# GasSensorCentral_v2_2.net
KiCad netlist of a schematic drawn in EAGLE
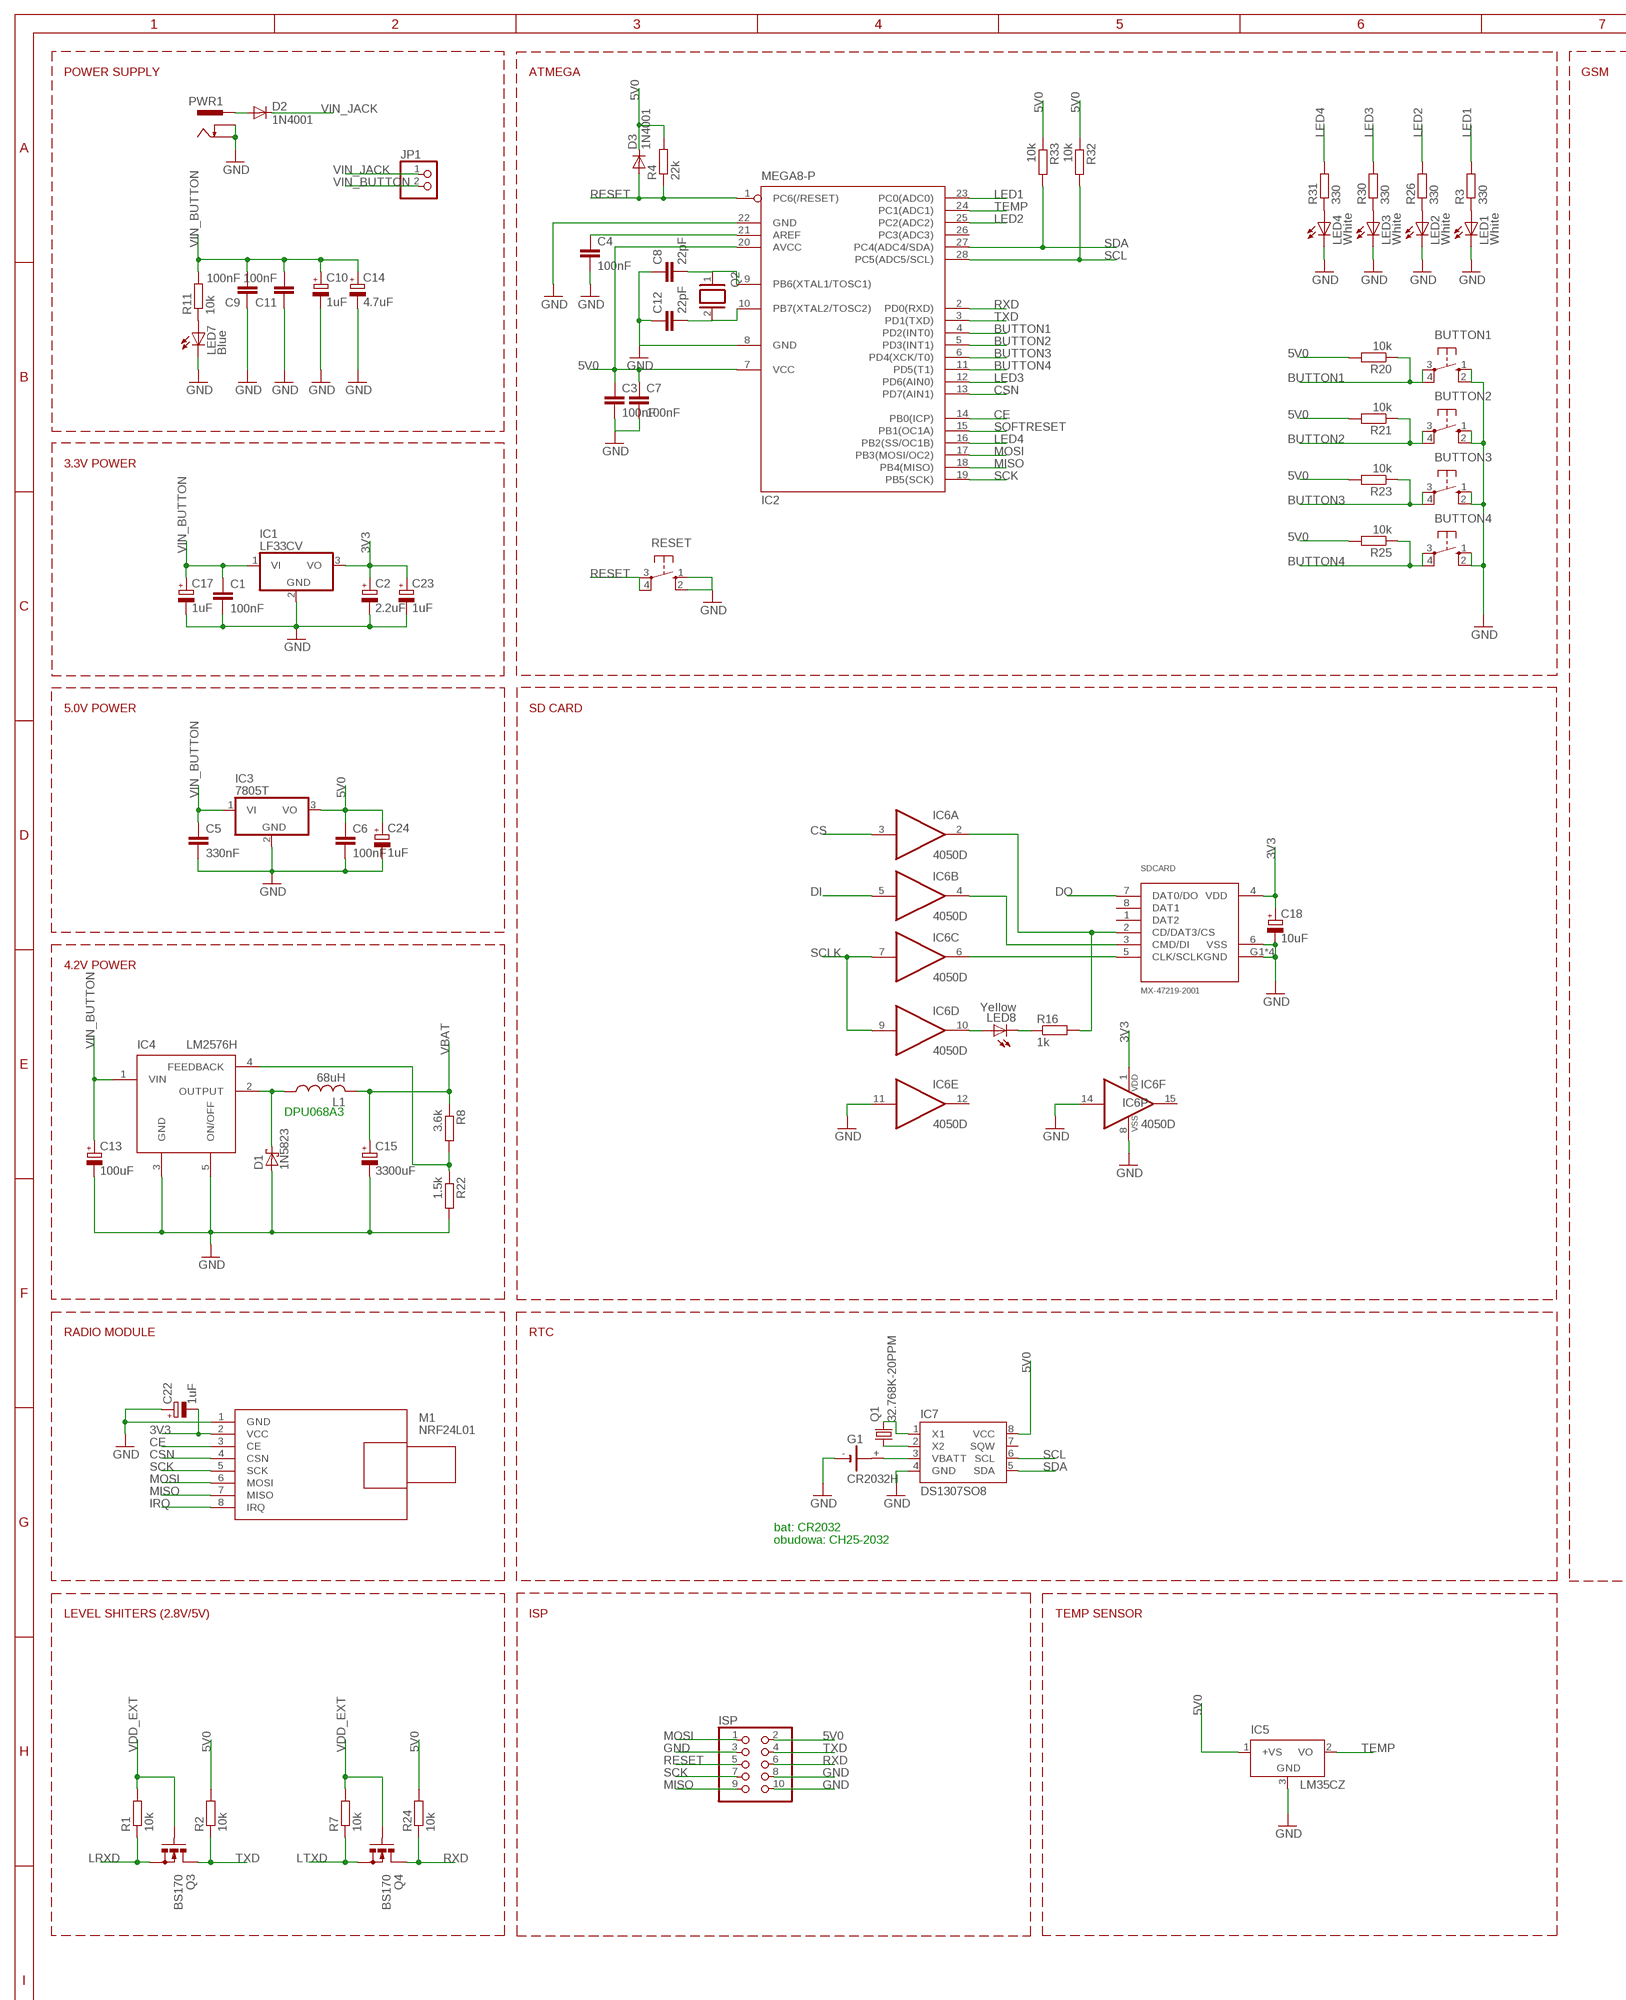
[diagram p0: schematic, sheet 1, part 1 of 2]
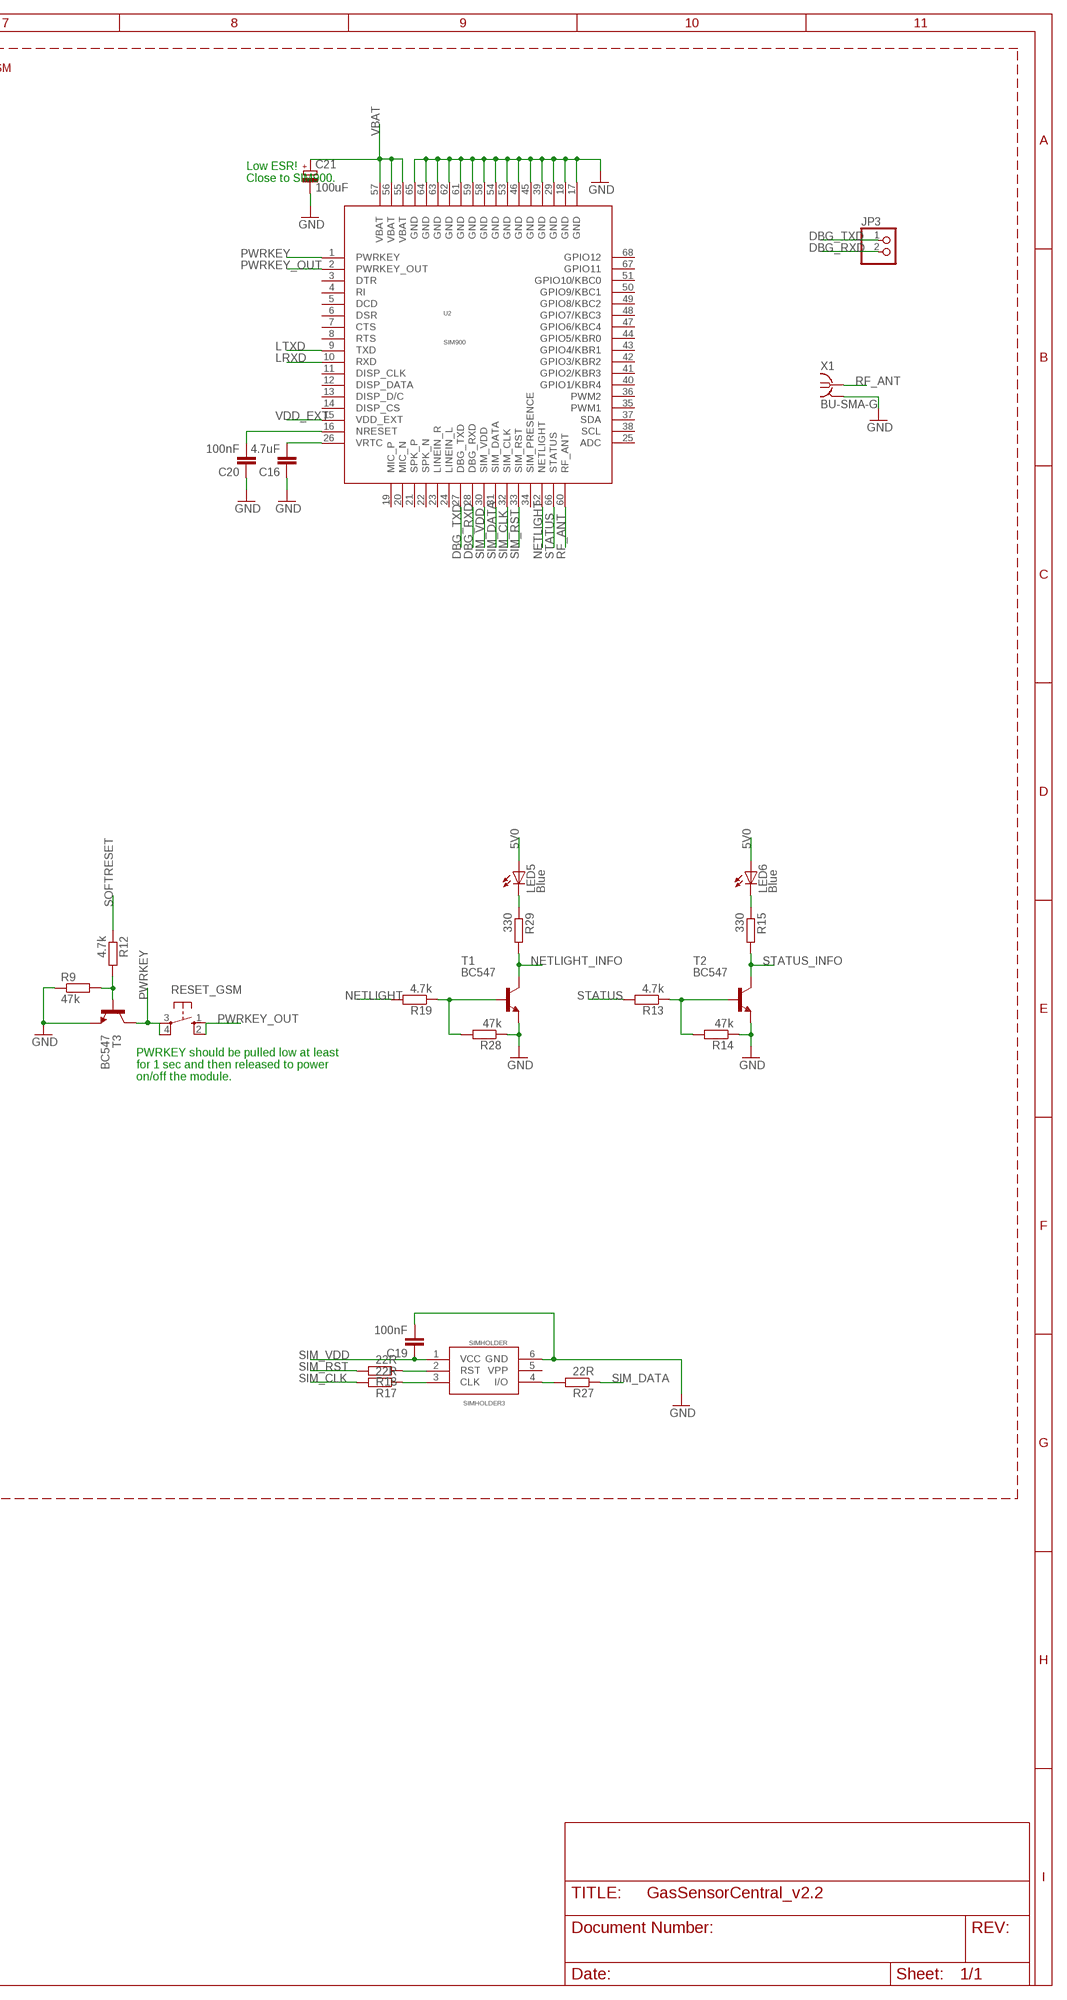
[diagram p1: schematic, sheet 1, part 2 of 2]

(export (version "E")
  (design (tool "Eeschema 10.0.6"))
  (components
    (comp (ref "BUTTON1")
      (value "10-XX")
      (footprint "eagle-import:B3F-10XX")
      (fields (field (name "MPN") "B3F-1000"))
      (libsource (lib "eagle-import") (part "10-XX"))
    )
    (comp (ref "BUTTON2")
      (value "10-XX")
      (footprint "eagle-import:B3F-10XX")
      (fields (field (name "MPN") "B3F-1000"))
      (libsource (lib "eagle-import") (part "10-XX"))
    )
    (comp (ref "BUTTON3")
      (value "10-XX")
      (footprint "eagle-import:B3F-10XX")
      (fields (field (name "MPN") "B3F-1000"))
      (libsource (lib "eagle-import") (part "10-XX"))
    )
    (comp (ref "BUTTON4")
      (value "10-XX")
      (footprint "eagle-import:B3F-10XX")
      (fields (field (name "MPN") "B3F-1000"))
      (libsource (lib "eagle-import") (part "10-XX"))
    )
    (comp (ref "C1")
      (value "100nF")
      (footprint "eagle-import:C025-025X050")
      (libsource (lib "eagle-import") (part "C-EU025-025X050"))
    )
    (comp (ref "C2")
      (value "2.2uF")
      (footprint "eagle-import:E2,5-5")
      (libsource (lib "eagle-import") (part "CPOL-EUE2.5-5"))
    )
    (comp (ref "C3")
      (value "100nF")
      (footprint "eagle-import:C025-025X050")
      (libsource (lib "eagle-import") (part "C-EU025-025X050"))
    )
    (comp (ref "C4")
      (value "100nF")
      (footprint "eagle-import:C025-025X050")
      (libsource (lib "eagle-import") (part "C-EU025-025X050"))
    )
    (comp (ref "C5")
      (value "330nF")
      (footprint "eagle-import:C025-025X050")
      (libsource (lib "eagle-import") (part "C-EU025-025X050"))
    )
    (comp (ref "C6")
      (value "100nF")
      (footprint "eagle-import:C025-025X050")
      (libsource (lib "eagle-import") (part "C-EU025-025X050"))
    )
    (comp (ref "C7")
      (value "100nF")
      (footprint "eagle-import:C025-025X050")
      (libsource (lib "eagle-import") (part "C-EU025-025X050"))
    )
    (comp (ref "C8")
      (value "22pF")
      (footprint "eagle-import:C025-025X050")
      (libsource (lib "eagle-import") (part "C-EU025-025X050"))
    )
    (comp (ref "C9")
      (value "100nF")
      (footprint "eagle-import:C025-025X050")
      (libsource (lib "eagle-import") (part "C-EU025-025X050"))
    )
    (comp (ref "C10")
      (value "1uF")
      (footprint "eagle-import:E2,5-5")
      (libsource (lib "eagle-import") (part "CPOL-EUE2.5-5"))
    )
    (comp (ref "C11")
      (value "100nF")
      (footprint "eagle-import:C025-025X050")
      (libsource (lib "eagle-import") (part "C-EU025-025X050"))
    )
    (comp (ref "C12")
      (value "22pF")
      (footprint "eagle-import:C025-025X050")
      (libsource (lib "eagle-import") (part "C-EU025-025X050"))
    )
    (comp (ref "C13")
      (value "100uF")
      (footprint "eagle-import:E2,5-5")
      (libsource (lib "eagle-import") (part "CPOL-EUE2.5-5"))
    )
    (comp (ref "C14")
      (value "4.7uF")
      (footprint "eagle-import:E2,5-5")
      (libsource (lib "eagle-import") (part "CPOL-EUE2.5-5"))
    )
    (comp (ref "C15")
      (value "3300uF")
      (footprint "eagle-import:E5-13")
      (libsource (lib "eagle-import") (part "CPOL-EUE5-13"))
    )
    (comp (ref "C16")
      (value "4.7uF")
      (footprint "eagle-import:C025-025X050")
      (libsource (lib "eagle-import") (part "C-EU025-025X050"))
    )
    (comp (ref "C17")
      (value "1uF")
      (footprint "eagle-import:E2,5-5")
      (libsource (lib "eagle-import") (part "CPOL-EUE2.5-5"))
    )
    (comp (ref "C18")
      (value "10uF")
      (footprint "eagle-import:E2,5-5")
      (libsource (lib "eagle-import") (part "CPOL-EUE2.5-5"))
    )
    (comp (ref "C19")
      (value "100nF")
      (footprint "eagle-import:C025-025X050")
      (libsource (lib "eagle-import") (part "C-EU025-025X050"))
    )
    (comp (ref "C20")
      (value "100nF")
      (footprint "eagle-import:C025-025X050")
      (libsource (lib "eagle-import") (part "C-EU025-025X050"))
    )
    (comp (ref "C21")
      (value "100uF")
      (footprint "eagle-import:E2,5-5")
      (libsource (lib "eagle-import") (part "CPOL-EUE2.5-5"))
    )
    (comp (ref "C22")
      (value "1uF")
      (footprint "eagle-import:E2,5-5")
      (libsource (lib "eagle-import") (part "CPOL-EUE2.5-5"))
    )
    (comp (ref "C23")
      (value "1uF")
      (footprint "eagle-import:E2,5-5")
      (libsource (lib "eagle-import") (part "CPOL-EUE2.5-5"))
    )
    (comp (ref "C24")
      (value "1uF")
      (footprint "eagle-import:E2,5-5")
      (libsource (lib "eagle-import") (part "CPOL-EUE2.5-5"))
    )
    (comp (ref "D1")
      (value "1N5823")
      (footprint "eagle-import:DO41-7.6")
      (libsource (lib "eagle-import") (part "1N5817-B"))
    )
    (comp (ref "D2")
      (value "1N4001")
      (footprint "eagle-import:DO41-10")
      (libsource (lib "eagle-import") (part "1N4004"))
    )
    (comp (ref "D3")
      (value "1N4001")
      (footprint "eagle-import:DO41-10")
      (libsource (lib "eagle-import") (part "1N4004"))
    )
    (comp (ref "G1")
      (value "CR2032H")
      (footprint "eagle-import:CR2032H")
      (libsource (lib "eagle-import") (part "CR2032H"))
    )
    (comp (ref "IC1")
      (value "LF33CV")
      (footprint "eagle-import:TO220H")
      (libsource (lib "eagle-import") (part "78T05"))
    )
    (comp (ref "IC2")
      (value "MEGA8-P")
      (footprint "eagle-import:DIL28-3")
      (libsource (lib "eagle-import") (part "MEGA8-P"))
    )
    (comp (ref "IC3")
      (value "7805T")
      (footprint "eagle-import:TO220H")
      (libsource (lib "eagle-import") (part "78T05"))
    )
    (comp (ref "IC4")
      (value "LM2576H")
      (footprint "eagle-import:TO220-52")
      (libsource (lib "eagle-import") (part "LM2576H"))
    )
    (comp (ref "IC5")
      (value "LM35CZ")
      (footprint "eagle-import:TO92")
      (libsource (lib "eagle-import") (part "LM35CZ"))
    )
    (comp (ref "IC6")
      (value "4050D")
      (footprint "eagle-import:SO16")
      (libsource (lib "eagle-import") (part "4050D"))
    )
    (comp (ref "IC7")
      (value "DS1307SO8")
      (footprint "eagle-import:SO08")
      (libsource (lib "eagle-import") (part "DS1307SO8"))
    )
    (comp (ref "ISP")
      (value "PINHD-2X5")
      (footprint "eagle-import:2X05")
      (libsource (lib "eagle-import") (part "PINHD-2X5"))
    )
    (comp (ref "JP1")
      (value "PINHD-1X2")
      (footprint "eagle-import:1X02")
      (libsource (lib "eagle-import") (part "PINHD-1X2"))
    )
    (comp (ref "JP3")
      (value "PINHD-1X2")
      (footprint "eagle-import:1X02")
      (libsource (lib "eagle-import") (part "PINHD-1X2"))
    )
    (comp (ref "L1")
      (value "68uH")
      (footprint "eagle-import:TJ4-U1")
      (libsource (lib "eagle-import") (part "L-USTJ4-U1"))
    )
    (comp (ref "LED1")
      (value "White")
      (footprint "eagle-import:LED3MM")
      (libsource (lib "eagle-import") (part "LED3MM"))
    )
    (comp (ref "LED2")
      (value "White")
      (footprint "eagle-import:LED3MM")
      (libsource (lib "eagle-import") (part "LED3MM"))
    )
    (comp (ref "LED3")
      (value "White")
      (footprint "eagle-import:LED3MM")
      (libsource (lib "eagle-import") (part "LED3MM"))
    )
    (comp (ref "LED4")
      (value "White")
      (footprint "eagle-import:LED3MM")
      (libsource (lib "eagle-import") (part "LED3MM"))
    )
    (comp (ref "LED5")
      (value "Blue")
      (footprint "eagle-import:LED3MM")
      (libsource (lib "eagle-import") (part "LED3MM"))
    )
    (comp (ref "LED6")
      (value "Blue")
      (footprint "eagle-import:LED3MM")
      (libsource (lib "eagle-import") (part "LED3MM"))
    )
    (comp (ref "LED7")
      (value "Blue")
      (footprint "eagle-import:LED3MM")
      (libsource (lib "eagle-import") (part "LED3MM"))
    )
    (comp (ref "LED8")
      (value "Yellow")
      (footprint "eagle-import:LED3MM")
      (libsource (lib "eagle-import") (part "LED3MM"))
    )
    (comp (ref "M1")
      (value "NRF24L01")
      (footprint "eagle-import:WIRELESS-NRD24L01-PA-EXT")
      (libsource (lib "eagle-import") (part "WIRELESS-NRF24L01-PA-EXT"))
    )
    (comp (ref "PWR1")
      (value "PWR-JAKPWR_JACK_UNI_MILLING")
      (footprint "eagle-import:PWR_JACK_UNI_MILLING")
      (libsource (lib "eagle-import") (part "PWR-JAKPWR_JACK_UNI_MILLING"))
    )
    (comp (ref "Q1")
      (value "32.768K-20PPM")
      (footprint "eagle-import:TC26V")
      (libsource (lib "eagle-import") (part "CRYSTALTC26V"))
    )
    (comp (ref "Q2")
      (value "XTAL/S")
      (footprint "eagle-import:QS")
      (libsource (lib "eagle-import") (part "XTAL/S"))
    )
    (comp (ref "Q3")
      (value "BS170")
      (footprint "eagle-import:SOT54E")
      (libsource (lib "eagle-import") (part "BS170"))
    )
    (comp (ref "Q4")
      (value "BS170")
      (footprint "eagle-import:SOT54E")
      (libsource (lib "eagle-import") (part "BS170"))
    )
    (comp (ref "R1")
      (value "10k")
      (footprint "eagle-import:0207_10")
      (libsource (lib "eagle-import") (part "R-EU_0207/10"))
    )
    (comp (ref "R2")
      (value "10k")
      (footprint "eagle-import:0207_10")
      (libsource (lib "eagle-import") (part "R-EU_0207/10"))
    )
    (comp (ref "R3")
      (value "330")
      (footprint "eagle-import:0207_10")
      (libsource (lib "eagle-import") (part "R-EU_0207/10"))
    )
    (comp (ref "R4")
      (value "22k")
      (footprint "eagle-import:0207_10")
      (libsource (lib "eagle-import") (part "R-EU_0207/10"))
    )
    (comp (ref "R7")
      (value "10k")
      (footprint "eagle-import:0207_10")
      (libsource (lib "eagle-import") (part "R-EU_0207/10"))
    )
    (comp (ref "R8")
      (value "3.6k")
      (footprint "eagle-import:0207_10")
      (libsource (lib "eagle-import") (part "R-EU_0207/10"))
    )
    (comp (ref "R9")
      (value "47k")
      (footprint "eagle-import:0207_10")
      (libsource (lib "eagle-import") (part "R-EU_0207/10"))
    )
    (comp (ref "R11")
      (value "10k")
      (footprint "eagle-import:0207_10")
      (libsource (lib "eagle-import") (part "R-EU_0207/10"))
    )
    (comp (ref "R12")
      (value "4.7k")
      (footprint "eagle-import:0207_10")
      (libsource (lib "eagle-import") (part "R-EU_0207/10"))
    )
    (comp (ref "R13")
      (value "4.7k")
      (footprint "eagle-import:0207_10")
      (libsource (lib "eagle-import") (part "R-EU_0207/10"))
    )
    (comp (ref "R14")
      (value "47k")
      (footprint "eagle-import:0207_10")
      (libsource (lib "eagle-import") (part "R-EU_0207/10"))
    )
    (comp (ref "R15")
      (value "330")
      (footprint "eagle-import:0207_10")
      (libsource (lib "eagle-import") (part "R-EU_0207/10"))
    )
    (comp (ref "R16")
      (value "1k")
      (footprint "eagle-import:0207_10")
      (libsource (lib "eagle-import") (part "R-EU_0207/10"))
    )
    (comp (ref "R17")
      (value "22R")
      (footprint "eagle-import:0207_10")
      (libsource (lib "eagle-import") (part "R-EU_0207/10"))
    )
    (comp (ref "R18")
      (value "22R")
      (footprint "eagle-import:0207_10")
      (libsource (lib "eagle-import") (part "R-EU_0207/10"))
    )
    (comp (ref "R19")
      (value "4.7k")
      (footprint "eagle-import:0207_10")
      (libsource (lib "eagle-import") (part "R-EU_0207/10"))
    )
    (comp (ref "R20")
      (value "10k")
      (footprint "eagle-import:0207_10")
      (libsource (lib "eagle-import") (part "R-EU_0207/10"))
    )
    (comp (ref "R21")
      (value "10k")
      (footprint "eagle-import:0207_10")
      (libsource (lib "eagle-import") (part "R-EU_0207/10"))
    )
    (comp (ref "R22")
      (value "1.5k")
      (footprint "eagle-import:0207_10")
      (libsource (lib "eagle-import") (part "R-EU_0207/10"))
    )
    (comp (ref "R23")
      (value "10k")
      (footprint "eagle-import:0207_10")
      (libsource (lib "eagle-import") (part "R-EU_0207/10"))
    )
    (comp (ref "R24")
      (value "10k")
      (footprint "eagle-import:0207_10")
      (libsource (lib "eagle-import") (part "R-EU_0207/10"))
    )
    (comp (ref "R25")
      (value "10k")
      (footprint "eagle-import:0207_10")
      (libsource (lib "eagle-import") (part "R-EU_0207/10"))
    )
    (comp (ref "R26")
      (value "330")
      (footprint "eagle-import:0207_10")
      (libsource (lib "eagle-import") (part "R-EU_0207/10"))
    )
    (comp (ref "R27")
      (value "22R")
      (footprint "eagle-import:0207_10")
      (libsource (lib "eagle-import") (part "R-EU_0207/10"))
    )
    (comp (ref "R28")
      (value "47k")
      (footprint "eagle-import:0207_10")
      (libsource (lib "eagle-import") (part "R-EU_0207/10"))
    )
    (comp (ref "R29")
      (value "330")
      (footprint "eagle-import:0207_10")
      (libsource (lib "eagle-import") (part "R-EU_0207/10"))
    )
    (comp (ref "R30")
      (value "330")
      (footprint "eagle-import:0207_10")
      (libsource (lib "eagle-import") (part "R-EU_0207/10"))
    )
    (comp (ref "R31")
      (value "330")
      (footprint "eagle-import:0207_10")
      (libsource (lib "eagle-import") (part "R-EU_0207/10"))
    )
    (comp (ref "R32")
      (value "10k")
      (footprint "eagle-import:0207_10")
      (libsource (lib "eagle-import") (part "R-EU_0207/10"))
    )
    (comp (ref "R33")
      (value "10k")
      (footprint "eagle-import:0207_10")
      (libsource (lib "eagle-import") (part "R-EU_0207/10"))
    )
    (comp (ref "RESET")
      (value "10-XX")
      (footprint "eagle-import:B3F-10XX")
      (fields (field (name "MPN") "B3F-1000"))
      (libsource (lib "eagle-import") (part "10-XX"))
    )
    (comp (ref "RESET_GSM")
      (value "10-XX")
      (footprint "eagle-import:B3F-10XX")
      (fields (field (name "MPN") "B3F-1000"))
      (libsource (lib "eagle-import") (part "10-XX"))
    )
    (comp (ref "SDCARD")
      (value "MX-47219-2001")
      (footprint "eagle-import:MX-47219-2001")
      (libsource (lib "eagle-import") (part "MX-47219-2001"))
    )
    (comp (ref "SIMHOLDER")
      (value "SIMHOLDER3")
      (footprint "eagle-import:SIMHOLDER3")
      (libsource (lib "eagle-import") (part "SIMHOLDER3"))
    )
    (comp (ref "T1")
      (value "BC547")
      (footprint "eagle-import:TO92")
      (libsource (lib "eagle-import") (part "BC547"))
    )
    (comp (ref "T2")
      (value "BC547")
      (footprint "eagle-import:TO92")
      (libsource (lib "eagle-import") (part "BC547"))
    )
    (comp (ref "T3")
      (value "BC547")
      (footprint "eagle-import:TO92")
      (libsource (lib "eagle-import") (part "BC547"))
    )
    (comp (ref "U2")
      (value "SIM900")
      (footprint "eagle-import:SIM900")
      (libsource (lib "eagle-import") (part "SIM900"))
    )
    (comp (ref "X1")
      (value "BU-SMA-G")
      (footprint "eagle-import:BU-SMA-G")
      (libsource (lib "eagle-import") (part "BU-SMA-G"))
    )
  )
  (nets
    (net (code "1") (name "/3V3") (class "Default")
      (node (ref "C18") (pin "+") (pinfunction "+_+") (pintype "passive"))
      (node (ref "C2") (pin "+") (pinfunction "+_+") (pintype "passive"))
      (node (ref "C22") (pin "-") (pinfunction "-_-") (pintype "passive"))
      (node (ref "C23") (pin "+") (pinfunction "+_+") (pintype "passive"))
      (node (ref "IC1") (pin "3") (pinfunction "VO_3") (pintype "passive"))
      (node (ref "IC6") (pin "1") (pinfunction "VDD_1") (pintype "power_in"))
      (node (ref "M1") (pin "2") (pinfunction "VCC_2") (pintype "power_in"))
      (node (ref "SDCARD") (pin "4") (pinfunction "VDD_4") (pintype "bidirectional"))
    )
    (net (code "2") (name "/5V0") (class "Default")
      (node (ref "C24") (pin "+") (pinfunction "+_+") (pintype "passive"))
      (node (ref "C3") (pin "1") (pinfunction "1_1") (pintype "passive"))
      (node (ref "C6") (pin "1") (pinfunction "1_1") (pintype "passive"))
      (node (ref "C7") (pin "1") (pinfunction "1_1") (pintype "passive"))
      (node (ref "D3") (pin "C") (pinfunction "C_C") (pintype "passive"))
      (node (ref "IC2") (pin "20") (pinfunction "AVCC_20") (pintype "power_in"))
      (node (ref "IC2") (pin "7") (pinfunction "VCC_7") (pintype "power_in"))
      (node (ref "IC3") (pin "3") (pinfunction "VO_3") (pintype "passive"))
      (node (ref "IC5") (pin "1") (pinfunction "+VS_1") (pintype "input"))
      (node (ref "IC7") (pin "8") (pinfunction "VCC_8") (pintype "bidirectional"))
      (node (ref "ISP") (pin "2") (pinfunction "2_2") (pintype "passive"))
      (node (ref "LED5") (pin "A") (pinfunction "A_A") (pintype "passive"))
      (node (ref "LED6") (pin "A") (pinfunction "A_A") (pintype "passive"))
      (node (ref "R2") (pin "2") (pinfunction "2_2") (pintype "passive"))
      (node (ref "R20") (pin "2") (pinfunction "2_2") (pintype "passive"))
      (node (ref "R21") (pin "2") (pinfunction "2_2") (pintype "passive"))
      (node (ref "R23") (pin "2") (pinfunction "2_2") (pintype "passive"))
      (node (ref "R24") (pin "2") (pinfunction "2_2") (pintype "passive"))
      (node (ref "R25") (pin "2") (pinfunction "2_2") (pintype "passive"))
      (node (ref "R32") (pin "1") (pinfunction "1_1") (pintype "passive"))
      (node (ref "R33") (pin "1") (pinfunction "1_1") (pintype "passive"))
      (node (ref "R4") (pin "2") (pinfunction "2_2") (pintype "passive"))
    )
    (net (code "3") (name "/BUTTON1") (class "Default")
      (node (ref "BUTTON1") (pin "3") (pinfunction "P_3") (pintype "passive"))
      (node (ref "BUTTON1") (pin "4") (pinfunction "P1_4") (pintype "passive"))
      (node (ref "IC2") (pin "4") (pinfunction "PD2(INT0)_4") (pintype "bidirectional"))
      (node (ref "R20") (pin "1") (pinfunction "1_1") (pintype "passive"))
    )
    (net (code "4") (name "/BUTTON2") (class "Default")
      (node (ref "BUTTON2") (pin "3") (pinfunction "P_3") (pintype "passive"))
      (node (ref "BUTTON2") (pin "4") (pinfunction "P1_4") (pintype "passive"))
      (node (ref "IC2") (pin "5") (pinfunction "PD3(INT1)_5") (pintype "bidirectional"))
      (node (ref "R21") (pin "1") (pinfunction "1_1") (pintype "passive"))
    )
    (net (code "5") (name "/BUTTON3") (class "Default")
      (node (ref "BUTTON3") (pin "3") (pinfunction "P_3") (pintype "passive"))
      (node (ref "BUTTON3") (pin "4") (pinfunction "P1_4") (pintype "passive"))
      (node (ref "IC2") (pin "6") (pinfunction "PD4(XCK/T0)_6") (pintype "bidirectional"))
      (node (ref "R23") (pin "1") (pinfunction "1_1") (pintype "passive"))
    )
    (net (code "6") (name "/BUTTON4") (class "Default")
      (node (ref "BUTTON4") (pin "3") (pinfunction "P_3") (pintype "passive"))
      (node (ref "BUTTON4") (pin "4") (pinfunction "P1_4") (pintype "passive"))
      (node (ref "IC2") (pin "11") (pinfunction "PD5(T1)_11") (pintype "bidirectional"))
      (node (ref "R25") (pin "1") (pinfunction "1_1") (pintype "passive"))
    )
    (net (code "7") (name "/CE") (class "Default")
      (node (ref "IC2") (pin "14") (pinfunction "PB0(ICP)_14") (pintype "bidirectional"))
      (node (ref "M1") (pin "3") (pinfunction "CE_3") (pintype "bidirectional"))
    )
    (net (code "8") (name "/CS") (class "Default")
      (node (ref "IC6") (pin "3") (pinfunction "I_3") (pintype "input"))
    )
    (net (code "9") (name "/CSN") (class "Default")
      (node (ref "IC2") (pin "13") (pinfunction "PD7(AIN1)_13") (pintype "bidirectional"))
      (node (ref "M1") (pin "4") (pinfunction "CSN_4") (pintype "bidirectional"))
    )
    (net (code "10") (name "/DBG_RXD") (class "Default")
      (node (ref "JP3") (pin "2") (pinfunction "2_2") (pintype "passive"))
      (node (ref "U2") (pin "28") (pinfunction "DBG_RXD_28") (pintype "input"))
    )
    (net (code "11") (name "/DBG_TXD") (class "Default")
      (node (ref "JP3") (pin "1") (pinfunction "1_1") (pintype "passive"))
      (node (ref "U2") (pin "27") (pinfunction "DBG_TXD_27") (pintype "output"))
    )
    (net (code "12") (name "/DI") (class "Default")
      (node (ref "IC6") (pin "5") (pinfunction "I_5") (pintype "input"))
    )
    (net (code "13") (name "/DO") (class "Default")
      (node (ref "SDCARD") (pin "7") (pinfunction "DAT0/DO_7") (pintype "bidirectional"))
    )
    (net (code "14") (name "/IRQ") (class "Default")
      (node (ref "M1") (pin "8") (pinfunction "IRQ_8") (pintype "bidirectional"))
    )
    (net (code "15") (name "/LED1") (class "Default")
      (node (ref "IC2") (pin "23") (pinfunction "PC0(ADC0)_23") (pintype "bidirectional"))
      (node (ref "R3") (pin "2") (pinfunction "2_2") (pintype "passive"))
    )
    (net (code "16") (name "/LED2") (class "Default")
      (node (ref "IC2") (pin "25") (pinfunction "PC2(ADC2)_25") (pintype "bidirectional"))
      (node (ref "R26") (pin "2") (pinfunction "2_2") (pintype "passive"))
    )
    (net (code "17") (name "/LED3") (class "Default")
      (node (ref "IC2") (pin "12") (pinfunction "PD6(AIN0)_12") (pintype "bidirectional"))
      (node (ref "R30") (pin "2") (pinfunction "2_2") (pintype "passive"))
    )
    (net (code "18") (name "/LED4") (class "Default")
      (node (ref "IC2") (pin "16") (pinfunction "PB2(SS/OC1B)_16") (pintype "bidirectional"))
      (node (ref "R31") (pin "2") (pinfunction "2_2") (pintype "passive"))
    )
    (net (code "19") (name "/LRXD") (class "Default")
      (node (ref "Q3") (pin "S") (pinfunction "S_S") (pintype "passive"))
      (node (ref "R1") (pin "1") (pinfunction "1_1") (pintype "passive"))
      (node (ref "U2") (pin "10") (pinfunction "RXD_10") (pintype "input"))
    )
    (net (code "20") (name "/LTXD") (class "Default")
      (node (ref "Q4") (pin "S") (pinfunction "S_S") (pintype "passive"))
      (node (ref "R7") (pin "1") (pinfunction "1_1") (pintype "passive"))
      (node (ref "U2") (pin "9") (pinfunction "TXD_9") (pintype "output"))
    )
    (net (code "21") (name "/MISO") (class "Default")
      (node (ref "IC2") (pin "18") (pinfunction "PB4(MISO)_18") (pintype "bidirectional"))
      (node (ref "ISP") (pin "9") (pinfunction "9_9") (pintype "passive"))
      (node (ref "M1") (pin "7") (pinfunction "MISO_7") (pintype "bidirectional"))
    )
    (net (code "22") (name "/MOSI") (class "Default")
      (node (ref "IC2") (pin "17") (pinfunction "PB3(MOSI/OC2)_17") (pintype "bidirectional"))
      (node (ref "ISP") (pin "1") (pinfunction "1_1") (pintype "passive"))
      (node (ref "M1") (pin "6") (pinfunction "MOSI_6") (pintype "bidirectional"))
    )
    (net (code "23") (name "/NETLIGHT") (class "Default")
      (node (ref "R19") (pin "2") (pinfunction "2_2") (pintype "passive"))
      (node (ref "U2") (pin "52") (pinfunction "NETLIGHT_52") (pintype "output"))
    )
    (net (code "24") (name "/NETLIGHT_INFO") (class "Default")
      (node (ref "R29") (pin "2") (pinfunction "2_2") (pintype "passive"))
      (node (ref "T1") (pin "3") (pinfunction "C_3") (pintype "passive"))
    )
    (net (code "25") (name "/PWRKEY") (class "Default")
      (node (ref "RESET_GSM") (pin "3") (pinfunction "P_3") (pintype "passive"))
      (node (ref "RESET_GSM") (pin "4") (pinfunction "P1_4") (pintype "passive"))
      (node (ref "T3") (pin "3") (pinfunction "C_3") (pintype "passive"))
      (node (ref "U2") (pin "1") (pinfunction "PWRKEY_1") (pintype "input"))
    )
    (net (code "26") (name "/PWRKEY_OUT") (class "Default")
      (node (ref "RESET_GSM") (pin "1") (pinfunction "S_1") (pintype "passive"))
      (node (ref "RESET_GSM") (pin "2") (pinfunction "S1_2") (pintype "passive"))
      (node (ref "U2") (pin "2") (pinfunction "PWRKEY_OUT_2") (pintype "output"))
    )
    (net (code "27") (name "/RESET") (class "Default")
      (node (ref "D3") (pin "A") (pinfunction "A_A") (pintype "passive"))
      (node (ref "IC2") (pin "1") (pinfunction "PC6(/RESET)_1") (pintype "bidirectional"))
      (node (ref "ISP") (pin "5") (pinfunction "5_5") (pintype "passive"))
      (node (ref "R4") (pin "1") (pinfunction "1_1") (pintype "passive"))
      (node (ref "RESET") (pin "3") (pinfunction "P_3") (pintype "passive"))
      (node (ref "RESET") (pin "4") (pinfunction "P1_4") (pintype "passive"))
    )
    (net (code "28") (name "/RF_ANT") (class "Default")
      (node (ref "U2") (pin "60") (pinfunction "RF_ANT_60") (pintype "bidirectional"))
      (node (ref "X1") (pin "1") (pinfunction "1_1") (pintype "passive"))
    )
    (net (code "29") (name "/RXD") (class "Default")
      (node (ref "IC2") (pin "2") (pinfunction "PD0(RXD)_2") (pintype "bidirectional"))
      (node (ref "ISP") (pin "6") (pinfunction "6_6") (pintype "passive"))
      (node (ref "Q4") (pin "D") (pinfunction "D_D") (pintype "passive"))
      (node (ref "R24") (pin "1") (pinfunction "1_1") (pintype "passive"))
    )
    (net (code "30") (name "/SCK") (class "Default")
      (node (ref "IC2") (pin "19") (pinfunction "PB5(SCK)_19") (pintype "bidirectional"))
      (node (ref "ISP") (pin "7") (pinfunction "7_7") (pintype "passive"))
      (node (ref "M1") (pin "5") (pinfunction "SCK_5") (pintype "bidirectional"))
    )
    (net (code "31") (name "/SCL") (class "Default")
      (node (ref "IC2") (pin "28") (pinfunction "PC5(ADC5/SCL)_28") (pintype "bidirectional"))
      (node (ref "IC7") (pin "6") (pinfunction "SCL_6") (pintype "bidirectional"))
      (node (ref "R32") (pin "2") (pinfunction "2_2") (pintype "passive"))
    )
    (net (code "32") (name "/SCLK") (class "Default")
      (node (ref "IC6") (pin "7") (pinfunction "I_7") (pintype "input"))
      (node (ref "IC6") (pin "9") (pinfunction "I_9") (pintype "input"))
    )
    (net (code "33") (name "/SDA") (class "Default")
      (node (ref "IC2") (pin "27") (pinfunction "PC4(ADC4/SDA)_27") (pintype "bidirectional"))
      (node (ref "IC7") (pin "5") (pinfunction "SDA_5") (pintype "bidirectional"))
      (node (ref "R33") (pin "2") (pinfunction "2_2") (pintype "passive"))
    )
    (net (code "34") (name "/SIM_CLK") (class "Default")
      (node (ref "R17") (pin "2") (pinfunction "2_2") (pintype "passive"))
      (node (ref "U2") (pin "32") (pinfunction "SIM_CLK_32") (pintype "output"))
    )
    (net (code "35") (name "/SIM_DATA") (class "Default")
      (node (ref "R27") (pin "1") (pinfunction "1_1") (pintype "passive"))
      (node (ref "U2") (pin "31") (pinfunction "SIM_DATA_31") (pintype "bidirectional"))
    )
    (net (code "36") (name "/SIM_RST") (class "Default")
      (node (ref "R18") (pin "2") (pinfunction "2_2") (pintype "passive"))
      (node (ref "U2") (pin "33") (pinfunction "SIM_RST_33") (pintype "output"))
    )
    (net (code "37") (name "/SIM_VDD") (class "Default")
      (node (ref "C19") (pin "1") (pinfunction "1_1") (pintype "passive"))
      (node (ref "SIMHOLDER") (pin "1") (pinfunction "VCC_1") (pintype "bidirectional"))
      (node (ref "U2") (pin "30") (pinfunction "SIM_VDD_30") (pintype "output"))
    )
    (net (code "38") (name "/SOFTRESET") (class "Default")
      (node (ref "IC2") (pin "15") (pinfunction "PB1(OC1A)_15") (pintype "bidirectional"))
      (node (ref "R12") (pin "1") (pinfunction "1_1") (pintype "passive"))
    )
    (net (code "39") (name "/STATUS") (class "Default")
      (node (ref "R13") (pin "2") (pinfunction "2_2") (pintype "passive"))
      (node (ref "U2") (pin "66") (pinfunction "STATUS_66") (pintype "output"))
    )
    (net (code "40") (name "/STATUS_INFO") (class "Default")
      (node (ref "R15") (pin "2") (pinfunction "2_2") (pintype "passive"))
      (node (ref "T2") (pin "3") (pinfunction "C_3") (pintype "passive"))
    )
    (net (code "41") (name "/TEMP") (class "Default")
      (node (ref "IC2") (pin "24") (pinfunction "PC1(ADC1)_24") (pintype "bidirectional"))
      (node (ref "IC5") (pin "2") (pinfunction "VO_2") (pintype "input"))
    )
    (net (code "42") (name "/TXD") (class "Default")
      (node (ref "IC2") (pin "3") (pinfunction "PD1(TXD)_3") (pintype "bidirectional"))
      (node (ref "ISP") (pin "4") (pinfunction "4_4") (pintype "passive"))
      (node (ref "Q3") (pin "D") (pinfunction "D_D") (pintype "passive"))
      (node (ref "R2") (pin "1") (pinfunction "1_1") (pintype "passive"))
    )
    (net (code "43") (name "/VBAT") (class "Default")
      (node (ref "C15") (pin "+") (pinfunction "+_+") (pintype "passive"))
      (node (ref "C21") (pin "+") (pinfunction "+_+") (pintype "passive"))
      (node (ref "L1") (pin "2") (pinfunction "2_2") (pintype "passive"))
      (node (ref "R8") (pin "1") (pinfunction "1_1") (pintype "passive"))
      (node (ref "U2") (pin "55") (pinfunction "VBAT_55") (pintype "power_in"))
      (node (ref "U2") (pin "56") (pinfunction "VBAT_56") (pintype "power_in"))
      (node (ref "U2") (pin "57") (pinfunction "VBAT_57") (pintype "power_in"))
    )
    (net (code "44") (name "/VDD_EXT") (class "Default")
      (node (ref "Q3") (pin "G") (pinfunction "G_G") (pintype "passive"))
      (node (ref "Q4") (pin "G") (pinfunction "G_G") (pintype "passive"))
      (node (ref "R1") (pin "2") (pinfunction "2_2") (pintype "passive"))
      (node (ref "R7") (pin "2") (pinfunction "2_2") (pintype "passive"))
      (node (ref "U2") (pin "15") (pinfunction "VDD_EXT_15") (pintype "output"))
    )
    (net (code "45") (name "/VIN_BUTTON") (class "Default")
      (node (ref "C1") (pin "1") (pinfunction "1_1") (pintype "passive"))
      (node (ref "C10") (pin "+") (pinfunction "+_+") (pintype "passive"))
      (node (ref "C11") (pin "2") (pinfunction "2_2") (pintype "passive"))
      (node (ref "C13") (pin "+") (pinfunction "+_+") (pintype "passive"))
      (node (ref "C14") (pin "+") (pinfunction "+_+") (pintype "passive"))
      (node (ref "C17") (pin "+") (pinfunction "+_+") (pintype "passive"))
      (node (ref "C5") (pin "1") (pinfunction "1_1") (pintype "passive"))
      (node (ref "C9") (pin "2") (pinfunction "2_2") (pintype "passive"))
      (node (ref "IC1") (pin "1") (pinfunction "VI_1") (pintype "input"))
      (node (ref "IC3") (pin "1") (pinfunction "VI_1") (pintype "input"))
      (node (ref "IC4") (pin "1") (pinfunction "VIN_1") (pintype "input"))
      (node (ref "JP1") (pin "2") (pinfunction "2_2") (pintype "passive"))
      (node (ref "R11") (pin "2") (pinfunction "2_2") (pintype "passive"))
    )
    (net (code "46") (name "/VIN_JACK") (class "Default")
      (node (ref "D2") (pin "C") (pinfunction "C_C") (pintype "passive"))
      (node (ref "JP1") (pin "1") (pinfunction "1_1") (pintype "passive"))
    )
    (net (code "47") (name "GND") (class "Default")
      (node (ref "BUTTON1") (pin "1") (pinfunction "S_1") (pintype "passive"))
      (node (ref "BUTTON1") (pin "2") (pinfunction "S1_2") (pintype "passive"))
      (node (ref "BUTTON2") (pin "1") (pinfunction "S_1") (pintype "passive"))
      (node (ref "BUTTON2") (pin "2") (pinfunction "S1_2") (pintype "passive"))
      (node (ref "BUTTON3") (pin "1") (pinfunction "S_1") (pintype "passive"))
      (node (ref "BUTTON3") (pin "2") (pinfunction "S1_2") (pintype "passive"))
      (node (ref "BUTTON4") (pin "1") (pinfunction "S_1") (pintype "passive"))
      (node (ref "BUTTON4") (pin "2") (pinfunction "S1_2") (pintype "passive"))
      (node (ref "C1") (pin "2") (pinfunction "2_2") (pintype "passive"))
      (node (ref "C10") (pin "-") (pinfunction "-_-") (pintype "passive"))
      (node (ref "C11") (pin "1") (pinfunction "1_1") (pintype "passive"))
      (node (ref "C12") (pin "1") (pinfunction "1_1") (pintype "passive"))
      (node (ref "C13") (pin "-") (pinfunction "-_-") (pintype "passive"))
      (node (ref "C14") (pin "-") (pinfunction "-_-") (pintype "passive"))
      (node (ref "C15") (pin "-") (pinfunction "-_-") (pintype "passive"))
      (node (ref "C16") (pin "1") (pinfunction "1_1") (pintype "passive"))
      (node (ref "C17") (pin "-") (pinfunction "-_-") (pintype "passive"))
      (node (ref "C18") (pin "-") (pinfunction "-_-") (pintype "passive"))
      (node (ref "C19") (pin "2") (pinfunction "2_2") (pintype "passive"))
      (node (ref "C2") (pin "-") (pinfunction "-_-") (pintype "passive"))
      (node (ref "C20") (pin "1") (pinfunction "1_1") (pintype "passive"))
      (node (ref "C21") (pin "-") (pinfunction "-_-") (pintype "passive"))
      (node (ref "C22") (pin "+") (pinfunction "+_+") (pintype "passive"))
      (node (ref "C23") (pin "-") (pinfunction "-_-") (pintype "passive"))
      (node (ref "C24") (pin "-") (pinfunction "-_-") (pintype "passive"))
      (node (ref "C3") (pin "2") (pinfunction "2_2") (pintype "passive"))
      (node (ref "C4") (pin "2") (pinfunction "2_2") (pintype "passive"))
      (node (ref "C5") (pin "2") (pinfunction "2_2") (pintype "passive"))
      (node (ref "C6") (pin "2") (pinfunction "2_2") (pintype "passive"))
      (node (ref "C7") (pin "2") (pinfunction "2_2") (pintype "passive"))
      (node (ref "C8") (pin "1") (pinfunction "1_1") (pintype "passive"))
      (node (ref "C9") (pin "1") (pinfunction "1_1") (pintype "passive"))
      (node (ref "D1") (pin "A") (pinfunction "A_A") (pintype "passive"))
      (node (ref "G1") (pin "-") (pinfunction "-_-") (pintype "passive"))
      (node (ref "IC1") (pin "2") (pinfunction "GND_2") (pintype "passive"))
      (node (ref "IC2") (pin "22") (pinfunction "GND_22") (pintype "power_in"))
      (node (ref "IC2") (pin "8") (pinfunction "GND_8") (pintype "power_in"))
      (node (ref "IC3") (pin "2") (pinfunction "GND_2") (pintype "passive"))
      (node (ref "IC4") (pin "3") (pinfunction "GND_3") (pintype "power_in"))
      (node (ref "IC4") (pin "5") (pinfunction "ON/OFF_5") (pintype "bidirectional"))
      (node (ref "IC5") (pin "3") (pinfunction "GND_3") (pintype "power_in"))
      (node (ref "IC6") (pin "11") (pinfunction "I_11") (pintype "input"))
      (node (ref "IC6") (pin "14") (pinfunction "I_14") (pintype "input"))
      (node (ref "IC6") (pin "8") (pinfunction "VSS_8") (pintype "power_in"))
      (node (ref "IC7") (pin "4") (pinfunction "GND_4") (pintype "bidirectional"))
      (node (ref "ISP") (pin "10") (pinfunction "10_10") (pintype "passive"))
      (node (ref "ISP") (pin "3") (pinfunction "3_3") (pintype "passive"))
      (node (ref "ISP") (pin "8") (pinfunction "8_8") (pintype "passive"))
      (node (ref "LED1") (pin "K") (pinfunction "C_K") (pintype "passive"))
      (node (ref "LED2") (pin "K") (pinfunction "C_K") (pintype "passive"))
      (node (ref "LED3") (pin "K") (pinfunction "C_K") (pintype "passive"))
      (node (ref "LED4") (pin "K") (pinfunction "C_K") (pintype "passive"))
      (node (ref "LED7") (pin "K") (pinfunction "C_K") (pintype "passive"))
      (node (ref "M1") (pin "1") (pinfunction "GND_1") (pintype "power_in"))
      (node (ref "PWR1") (pin "-") (pinfunction "-_-") (pintype "passive"))
      (node (ref "PWR1") (pin "--") (pinfunction "--_--") (pintype "passive"))
      (node (ref "R14") (pin "1") (pinfunction "1_1") (pintype "passive"))
      (node (ref "R22") (pin "2") (pinfunction "2_2") (pintype "passive"))
      (node (ref "R28") (pin "1") (pinfunction "1_1") (pintype "passive"))
      (node (ref "R9") (pin "1") (pinfunction "1_1") (pintype "passive"))
      (node (ref "RESET") (pin "1") (pinfunction "S_1") (pintype "passive"))
      (node (ref "RESET") (pin "2") (pinfunction "S1_2") (pintype "passive"))
      (node (ref "SDCARD") (pin "6") (pinfunction "VSS_6") (pintype "bidirectional"))
      (node (ref "SDCARD") (pin "G1") (pinfunction "GND_G1") (pintype "bidirectional"))
      (node (ref "SDCARD") (pin "G2") (pinfunction "GND_G2") (pintype "bidirectional"))
      (node (ref "SDCARD") (pin "G3") (pinfunction "GND_G3") (pintype "bidirectional"))
      (node (ref "SDCARD") (pin "G4") (pinfunction "GND_G4") (pintype "bidirectional"))
      (node (ref "SIMHOLDER") (pin "6") (pinfunction "GND_6") (pintype "bidirectional"))
      (node (ref "T1") (pin "1") (pinfunction "E_1") (pintype "passive"))
      (node (ref "T2") (pin "1") (pinfunction "E_1") (pintype "passive"))
      (node (ref "T3") (pin "1") (pinfunction "E_1") (pintype "passive"))
      (node (ref "U2") (pin "17") (pinfunction "GND_17") (pintype "power_in"))
      (node (ref "U2") (pin "18") (pinfunction "GND_18") (pintype "power_in"))
      (node (ref "U2") (pin "29") (pinfunction "GND_29") (pintype "power_in"))
      (node (ref "U2") (pin "39") (pinfunction "GND_39") (pintype "power_in"))
      (node (ref "U2") (pin "45") (pinfunction "GND_45") (pintype "power_in"))
      (node (ref "U2") (pin "46") (pinfunction "GND_46") (pintype "power_in"))
      (node (ref "U2") (pin "53") (pinfunction "GND_53") (pintype "power_in"))
      (node (ref "U2") (pin "54") (pinfunction "GND_54") (pintype "power_in"))
      (node (ref "U2") (pin "58") (pinfunction "GND_58") (pintype "power_in"))
      (node (ref "U2") (pin "59") (pinfunction "GND_59") (pintype "power_in"))
      (node (ref "U2") (pin "61") (pinfunction "GND_61") (pintype "power_in"))
      (node (ref "U2") (pin "62") (pinfunction "GND_62") (pintype "power_in"))
      (node (ref "U2") (pin "63") (pinfunction "GND_63") (pintype "power_in"))
      (node (ref "U2") (pin "64") (pinfunction "GND_64") (pintype "power_in"))
      (node (ref "U2") (pin "65") (pinfunction "GND_65") (pintype "power_in"))
      (node (ref "X1") (pin "2") (pinfunction "2_2") (pintype "passive"))
      (node (ref "X1") (pin "3") (pinfunction "2_3") (pintype "passive"))
      (node (ref "X1") (pin "4") (pinfunction "2_4") (pintype "passive"))
      (node (ref "X1") (pin "5") (pinfunction "2_5") (pintype "passive"))
    )
    (net (code "48") (name "Net-(D2-PadA)") (class "Default")
      (node (ref "D2") (pin "A") (pinfunction "A_A") (pintype "passive"))
      (node (ref "PWR1") (pin "+") (pinfunction "+_+") (pintype "passive"))
    )
    (net (code "49") (name "Net-(IC2-AREF)") (class "Default")
      (node (ref "C4") (pin "1") (pinfunction "1_1") (pintype "passive"))
      (node (ref "IC2") (pin "21") (pinfunction "AREF_21") (pintype "passive"))
    )
    (net (code "50") (name "Net-(IC2-PB6(XTAL1{slash}TOSC1))") (class "Default")
      (node (ref "C8") (pin "2") (pinfunction "2_2") (pintype "passive"))
      (node (ref "IC2") (pin "9") (pinfunction "PB6(XTAL1/TOSC1)_9") (pintype "bidirectional"))
      (node (ref "Q2") (pin "1") (pinfunction "1_1") (pintype "passive"))
    )
    (net (code "51") (name "Net-(IC2-PB7(XTAL2{slash}TOSC2))") (class "Default")
      (node (ref "C12") (pin "2") (pinfunction "2_2") (pintype "passive"))
      (node (ref "IC2") (pin "10") (pinfunction "PB7(XTAL2/TOSC2)_10") (pintype "bidirectional"))
      (node (ref "Q2") (pin "2") (pinfunction "2_2") (pintype "passive"))
    )
    (net (code "52") (name "Net-(IC4-FEEDBACK)") (class "Default")
      (node (ref "IC4") (pin "4") (pinfunction "FEEDBACK_4") (pintype "bidirectional"))
      (node (ref "R22") (pin "1") (pinfunction "1_1") (pintype "passive"))
      (node (ref "R8") (pin "2") (pinfunction "2_2") (pintype "passive"))
    )
    (net (code "53") (name "Net-(IC4-OUTPUT)") (class "Default")
      (node (ref "D1") (pin "C") (pinfunction "C_C") (pintype "passive"))
      (node (ref "IC4") (pin "2") (pinfunction "OUTPUT_2") (pintype "output"))
      (node (ref "L1") (pin "1") (pinfunction "1_1") (pintype "passive"))
    )
    (net (code "54") (name "Net-(IC6A-O)") (class "Default")
      (node (ref "IC6") (pin "2") (pinfunction "O_2") (pintype "output"))
      (node (ref "R16") (pin "2") (pinfunction "2_2") (pintype "passive"))
      (node (ref "SDCARD") (pin "2") (pinfunction "CD/DAT3/CS_2") (pintype "bidirectional"))
    )
    (net (code "55") (name "Net-(IC6B-O)") (class "Default")
      (node (ref "IC6") (pin "4") (pinfunction "O_4") (pintype "output"))
      (node (ref "SDCARD") (pin "3") (pinfunction "CMD/DI_3") (pintype "bidirectional"))
    )
    (net (code "56") (name "Net-(IC6C-O)") (class "Default")
      (node (ref "IC6") (pin "6") (pinfunction "O_6") (pintype "output"))
      (node (ref "SDCARD") (pin "5") (pinfunction "CLK/SCLK_5") (pintype "bidirectional"))
    )
    (net (code "57") (name "Net-(IC6D-O)") (class "Default")
      (node (ref "IC6") (pin "10") (pinfunction "O_10") (pintype "output"))
      (node (ref "LED8") (pin "A") (pinfunction "A_A") (pintype "passive"))
    )
    (net (code "58") (name "Net-(IC7-VBATT)") (class "Default")
      (node (ref "G1") (pin "+") (pinfunction "+_+") (pintype "passive"))
      (node (ref "IC7") (pin "3") (pinfunction "VBATT_3") (pintype "bidirectional"))
    )
    (net (code "59") (name "Net-(IC7-X1)") (class "Default")
      (node (ref "IC7") (pin "1") (pinfunction "X1_1") (pintype "bidirectional"))
      (node (ref "Q1") (pin "2") (pinfunction "2_2") (pintype "passive"))
    )
    (net (code "60") (name "Net-(IC7-X2)") (class "Default")
      (node (ref "IC7") (pin "2") (pinfunction "X2_2") (pintype "bidirectional"))
      (node (ref "Q1") (pin "1") (pinfunction "1_1") (pintype "passive"))
    )
    (net (code "61") (name "Net-(LED1-PadA)") (class "Default")
      (node (ref "LED1") (pin "A") (pinfunction "A_A") (pintype "passive"))
      (node (ref "R3") (pin "1") (pinfunction "1_1") (pintype "passive"))
    )
    (net (code "62") (name "Net-(LED2-PadA)") (class "Default")
      (node (ref "LED2") (pin "A") (pinfunction "A_A") (pintype "passive"))
      (node (ref "R26") (pin "1") (pinfunction "1_1") (pintype "passive"))
    )
    (net (code "63") (name "Net-(LED3-PadA)") (class "Default")
      (node (ref "LED3") (pin "A") (pinfunction "A_A") (pintype "passive"))
      (node (ref "R30") (pin "1") (pinfunction "1_1") (pintype "passive"))
    )
    (net (code "64") (name "Net-(LED4-PadA)") (class "Default")
      (node (ref "LED4") (pin "A") (pinfunction "A_A") (pintype "passive"))
      (node (ref "R31") (pin "1") (pinfunction "1_1") (pintype "passive"))
    )
    (net (code "65") (name "Net-(LED5-C)") (class "Default")
      (node (ref "LED5") (pin "K") (pinfunction "C_K") (pintype "passive"))
      (node (ref "R29") (pin "1") (pinfunction "1_1") (pintype "passive"))
    )
    (net (code "66") (name "Net-(LED6-C)") (class "Default")
      (node (ref "LED6") (pin "K") (pinfunction "C_K") (pintype "passive"))
      (node (ref "R15") (pin "1") (pinfunction "1_1") (pintype "passive"))
    )
    (net (code "67") (name "Net-(LED7-PadA)") (class "Default")
      (node (ref "LED7") (pin "A") (pinfunction "A_A") (pintype "passive"))
      (node (ref "R11") (pin "1") (pinfunction "1_1") (pintype "passive"))
    )
    (net (code "68") (name "Net-(LED8-C)") (class "Default")
      (node (ref "LED8") (pin "K") (pinfunction "C_K") (pintype "passive"))
      (node (ref "R16") (pin "1") (pinfunction "1_1") (pintype "passive"))
    )
    (net (code "69") (name "Net-(SIMHOLDER-CLK)") (class "Default")
      (node (ref "R17") (pin "1") (pinfunction "1_1") (pintype "passive"))
      (node (ref "SIMHOLDER") (pin "3") (pinfunction "CLK_3") (pintype "bidirectional"))
    )
    (net (code "70") (name "Net-(SIMHOLDER-I{slash}O)") (class "Default")
      (node (ref "R27") (pin "2") (pinfunction "2_2") (pintype "passive"))
      (node (ref "SIMHOLDER") (pin "4") (pinfunction "I/O_4") (pintype "bidirectional"))
    )
    (net (code "71") (name "Net-(SIMHOLDER-RST)") (class "Default")
      (node (ref "R18") (pin "1") (pinfunction "1_1") (pintype "passive"))
      (node (ref "SIMHOLDER") (pin "2") (pinfunction "RST_2") (pintype "bidirectional"))
    )
    (net (code "72") (name "Net-(T1-B)") (class "Default")
      (node (ref "R19") (pin "1") (pinfunction "1_1") (pintype "passive"))
      (node (ref "R28") (pin "2") (pinfunction "2_2") (pintype "passive"))
      (node (ref "T1") (pin "2") (pinfunction "B_2") (pintype "passive"))
    )
    (net (code "73") (name "Net-(T2-B)") (class "Default")
      (node (ref "R13") (pin "1") (pinfunction "1_1") (pintype "passive"))
      (node (ref "R14") (pin "2") (pinfunction "2_2") (pintype "passive"))
      (node (ref "T2") (pin "2") (pinfunction "B_2") (pintype "passive"))
    )
    (net (code "74") (name "Net-(T3-B)") (class "Default")
      (node (ref "R12") (pin "2") (pinfunction "2_2") (pintype "passive"))
      (node (ref "R9") (pin "2") (pinfunction "2_2") (pintype "passive"))
      (node (ref "T3") (pin "2") (pinfunction "B_2") (pintype "passive"))
    )
    (net (code "75") (name "Net-(U2-NRESET)") (class "Default")
      (node (ref "C20") (pin "2") (pinfunction "2_2") (pintype "passive"))
      (node (ref "U2") (pin "16") (pinfunction "NRESET_16") (pintype "input"))
    )
    (net (code "76") (name "Net-(U2-VRTC)") (class "Default")
      (node (ref "C16") (pin "2") (pinfunction "2_2") (pintype "passive"))
      (node (ref "U2") (pin "26") (pinfunction "VRTC_26") (pintype "bidirectional"))
    )
    (net (code "77") (name "unconnected-(IC2-PC3(ADC3)-Pad26)") (class "Default")
      (node (ref "IC2") (pin "26") (pinfunction "PC3(ADC3)_26") (pintype "bidirectional"))
    )
    (net (code "78") (name "unconnected-(IC6E-O-Pad12)") (class "Default")
      (node (ref "IC6") (pin "12") (pinfunction "O_12") (pintype "output"))
    )
    (net (code "79") (name "unconnected-(IC6F-O-Pad15)") (class "Default")
      (node (ref "IC6") (pin "15") (pinfunction "O_15") (pintype "output"))
    )
    (net (code "80") (name "unconnected-(IC7-SQW-Pad7)") (class "Default")
      (node (ref "IC7") (pin "7") (pinfunction "SQW_7") (pintype "bidirectional"))
    )
    (net (code "81") (name "unconnected-(SDCARD-DAT1-Pad8)") (class "Default")
      (node (ref "SDCARD") (pin "8") (pinfunction "DAT1_8") (pintype "bidirectional"))
    )
    (net (code "82") (name "unconnected-(SDCARD-DAT2-Pad1)") (class "Default")
      (node (ref "SDCARD") (pin "1") (pinfunction "DAT2_1") (pintype "bidirectional"))
    )
    (net (code "83") (name "unconnected-(SIMHOLDER-VPP-Pad5)") (class "Default")
      (node (ref "SIMHOLDER") (pin "5") (pinfunction "VPP_5") (pintype "bidirectional"))
    )
    (net (code "84") (name "unconnected-(U2-ADC-Pad25)") (class "Default")
      (node (ref "U2") (pin "25") (pinfunction "ADC_25") (pintype "input"))
    )
    (net (code "85") (name "unconnected-(U2-CTS-Pad7)") (class "Default")
      (node (ref "U2") (pin "7") (pinfunction "CTS_7") (pintype "output"))
    )
    (net (code "86") (name "unconnected-(U2-DCD-Pad5)") (class "Default")
      (node (ref "U2") (pin "5") (pinfunction "DCD_5") (pintype "output"))
    )
    (net (code "87") (name "unconnected-(U2-DISP_CLK-Pad11)") (class "Default")
      (node (ref "U2") (pin "11") (pinfunction "DISP_CLK_11") (pintype "output"))
    )
    (net (code "88") (name "unconnected-(U2-DISP_CS-Pad14)") (class "Default")
      (node (ref "U2") (pin "14") (pinfunction "DISP_CS_14") (pintype "output"))
    )
    (net (code "89") (name "unconnected-(U2-DISP_DATA-Pad12)") (class "Default")
      (node (ref "U2") (pin "12") (pinfunction "DISP_DATA_12") (pintype "bidirectional"))
    )
    (net (code "90") (name "unconnected-(U2-DISP_D{slash}C-Pad13)") (class "Default")
      (node (ref "U2") (pin "13") (pinfunction "DISP_D/C_13") (pintype "output"))
    )
    (net (code "91") (name "unconnected-(U2-DSR-Pad6)") (class "Default")
      (node (ref "U2") (pin "6") (pinfunction "DSR_6") (pintype "output"))
    )
    (net (code "92") (name "unconnected-(U2-DTR-Pad3)") (class "Default")
      (node (ref "U2") (pin "3") (pinfunction "DTR_3") (pintype "input"))
    )
    (net (code "93") (name "unconnected-(U2-GPIO1{slash}KBR4-Pad40)") (class "Default")
      (node (ref "U2") (pin "40") (pinfunction "GPIO1/KBR4_40") (pintype "output"))
    )
    (net (code "94") (name "unconnected-(U2-GPIO2{slash}KBR3-Pad41)") (class "Default")
      (node (ref "U2") (pin "41") (pinfunction "GPIO2/KBR3_41") (pintype "output"))
    )
    (net (code "95") (name "unconnected-(U2-GPIO3{slash}KBR2-Pad42)") (class "Default")
      (node (ref "U2") (pin "42") (pinfunction "GPIO3/KBR2_42") (pintype "output"))
    )
    (net (code "96") (name "unconnected-(U2-GPIO4{slash}KBR1-Pad43)") (class "Default")
      (node (ref "U2") (pin "43") (pinfunction "GPIO4/KBR1_43") (pintype "output"))
    )
    (net (code "97") (name "unconnected-(U2-GPIO5{slash}KBR0-Pad44)") (class "Default")
      (node (ref "U2") (pin "44") (pinfunction "GPIO5/KBR0_44") (pintype "output"))
    )
    (net (code "98") (name "unconnected-(U2-GPIO6{slash}KBC4-Pad47)") (class "Default")
      (node (ref "U2") (pin "47") (pinfunction "GPIO6/KBC4_47") (pintype "input"))
    )
    (net (code "99") (name "unconnected-(U2-GPIO7{slash}KBC3-Pad48)") (class "Default")
      (node (ref "U2") (pin "48") (pinfunction "GPIO7/KBC3_48") (pintype "bidirectional"))
    )
    (net (code "100") (name "unconnected-(U2-GPIO8{slash}KBC2-Pad49)") (class "Default")
      (node (ref "U2") (pin "49") (pinfunction "GPIO8/KBC2_49") (pintype "input"))
    )
    (net (code "101") (name "unconnected-(U2-GPIO9{slash}KBC1-Pad50)") (class "Default")
      (node (ref "U2") (pin "50") (pinfunction "GPIO9/KBC1_50") (pintype "input"))
    )
    (net (code "102") (name "unconnected-(U2-GPIO10{slash}KBC0-Pad51)") (class "Default")
      (node (ref "U2") (pin "51") (pinfunction "GPIO10/KBC0_51") (pintype "bidirectional"))
    )
    (net (code "103") (name "unconnected-(U2-GPIO11-Pad67)") (class "Default")
      (node (ref "U2") (pin "67") (pinfunction "GPIO11_67") (pintype "bidirectional"))
    )
    (net (code "104") (name "unconnected-(U2-GPIO12-Pad68)") (class "Default")
      (node (ref "U2") (pin "68") (pinfunction "GPIO12_68") (pintype "bidirectional"))
    )
    (net (code "105") (name "unconnected-(U2-LINEIN_L-Pad24)") (class "Default")
      (node (ref "U2") (pin "24") (pinfunction "LINEIN_L_24") (pintype "input"))
    )
    (net (code "106") (name "unconnected-(U2-LINEIN_R-Pad23)") (class "Default")
      (node (ref "U2") (pin "23") (pinfunction "LINEIN_R_23") (pintype "input"))
    )
    (net (code "107") (name "unconnected-(U2-MIC_N-Pad20)") (class "Default")
      (node (ref "U2") (pin "20") (pinfunction "MIC_N_20") (pintype "input"))
    )
    (net (code "108") (name "unconnected-(U2-MIC_P-Pad19)") (class "Default")
      (node (ref "U2") (pin "19") (pinfunction "MIC_P_19") (pintype "input"))
    )
    (net (code "109") (name "unconnected-(U2-PWM1-Pad35)") (class "Default")
      (node (ref "U2") (pin "35") (pinfunction "PWM1_35") (pintype "output"))
    )
    (net (code "110") (name "unconnected-(U2-PWM2-Pad36)") (class "Default")
      (node (ref "U2") (pin "36") (pinfunction "PWM2_36") (pintype "output"))
    )
    (net (code "111") (name "unconnected-(U2-RI-Pad4)") (class "Default")
      (node (ref "U2") (pin "4") (pinfunction "RI_4") (pintype "output"))
    )
    (net (code "112") (name "unconnected-(U2-RTS-Pad8)") (class "Default")
      (node (ref "U2") (pin "8") (pinfunction "RTS_8") (pintype "input"))
    )
    (net (code "113") (name "unconnected-(U2-SCL-Pad38)") (class "Default")
      (node (ref "U2") (pin "38") (pinfunction "SCL_38") (pintype "output"))
    )
    (net (code "114") (name "unconnected-(U2-SDA-Pad37)") (class "Default")
      (node (ref "U2") (pin "37") (pinfunction "SDA_37") (pintype "bidirectional"))
    )
    (net (code "115") (name "unconnected-(U2-SIM_PRESENCE-Pad34)") (class "Default")
      (node (ref "U2") (pin "34") (pinfunction "SIM_PRESENCE_34") (pintype "input"))
    )
    (net (code "116") (name "unconnected-(U2-SPK_N-Pad22)") (class "Default")
      (node (ref "U2") (pin "22") (pinfunction "SPK_N_22") (pintype "output"))
    )
    (net (code "117") (name "unconnected-(U2-SPK_P-Pad21)") (class "Default")
      (node (ref "U2") (pin "21") (pinfunction "SPK_P_21") (pintype "output"))
    )
  )
)
